# Grove_-_3-axis_analog_accelerometer.net
KiCad netlist of a schematic drawn in EAGLE
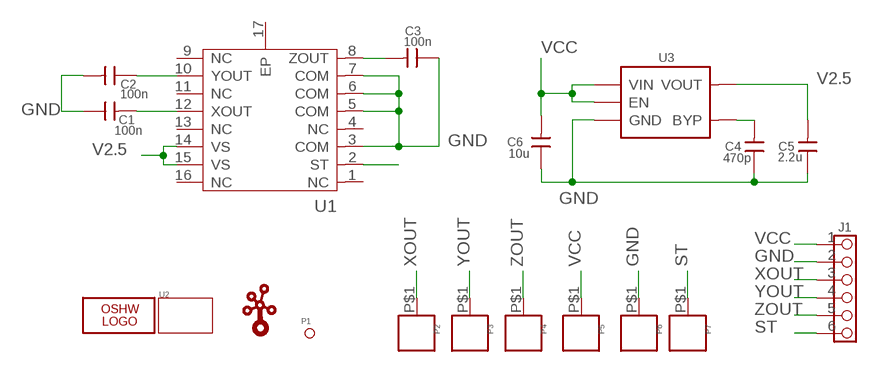
[diagram p0: schematic, sheet 1]

(export (version "E")
  (design (tool "Eeschema 10.0.6"))
  (components
    (comp (ref "C1")
      (value "100n")
      (footprint "eagle-import:0402")
      (libsource (lib "eagle-import") (part "C-0402"))
    )
    (comp (ref "C2")
      (value "100n")
      (footprint "eagle-import:0402")
      (libsource (lib "eagle-import") (part "C-0402"))
    )
    (comp (ref "C3")
      (value "100n")
      (footprint "eagle-import:0402")
      (libsource (lib "eagle-import") (part "C-0402"))
    )
    (comp (ref "C4")
      (value "470p")
      (footprint "eagle-import:0603")
      (libsource (lib "eagle-import") (part "C-0603"))
    )
    (comp (ref "C5")
      (value "2.2u")
      (footprint "eagle-import:0603")
      (libsource (lib "eagle-import") (part "C-0603"))
    )
    (comp (ref "C6")
      (value "10u")
      (footprint "eagle-import:0603")
      (libsource (lib "eagle-import") (part "C-0603"))
    )
    (comp (ref "J1")
      (value "HEADER-6P-60/35MIL")
      (footprint "eagle-import:6P-2.54-60_35MIL")
      (libsource (lib "eagle-import") (part "HEADER-6P-60/35MIL"))
    )
    (comp (ref "LOGO2")
      (value "LOGO-OSHW-6MILX0200-NT")
      (footprint "eagle-import:OSHW_6X200_NOTEXT")
      (libsource (lib "eagle-import") (part "LOGO-OSHW-6MILX0200-NT"))
    )
    (comp (ref "P1")
      (value "PAD-MARK")
      (footprint "eagle-import:ROUND-MARK-0.635")
      (libsource (lib "eagle-import") (part "PAD-MARK"))
    )
    (comp (ref "P2")
      (value "PAD'1X2MM'")
      (footprint "eagle-import:1P-1X2")
      (libsource (lib "eagle-import") (part "PAD'1X2MM'"))
    )
    (comp (ref "P3")
      (value "PAD'1X2MM'")
      (footprint "eagle-import:1P-1X2")
      (libsource (lib "eagle-import") (part "PAD'1X2MM'"))
    )
    (comp (ref "P4")
      (value "PAD'1X2MM'")
      (footprint "eagle-import:1P-1X2")
      (libsource (lib "eagle-import") (part "PAD'1X2MM'"))
    )
    (comp (ref "P5")
      (value "PAD'1X2MM'")
      (footprint "eagle-import:1P-1X2")
      (libsource (lib "eagle-import") (part "PAD'1X2MM'"))
    )
    (comp (ref "P6")
      (value "PAD'1X2MM'")
      (footprint "eagle-import:1P-1X2")
      (libsource (lib "eagle-import") (part "PAD'1X2MM'"))
    )
    (comp (ref "P7")
      (value "PAD'1X2MM'")
      (footprint "eagle-import:1P-1X2")
      (libsource (lib "eagle-import") (part "PAD'1X2MM'"))
    )
    (comp (ref "U$1")
      (value "LOGO-TWIGTWIGLOGO_SMALL")
      (footprint "eagle-import:TWIGLOGO_SMALL")
      (libsource (lib "eagle-import") (part "LOGO-TWIGTWIGLOGO_SMALL"))
    )
    (comp (ref "U1")
      (value "ADXL335")
      (footprint "eagle-import:LFCSP16-4X4")
      (libsource (lib "eagle-import") (part "ADXL335"))
    )
    (comp (ref "U2")
      (value "TWIG-1U")
      (footprint "eagle-import:1U-DIM-W_-DRILL")
      (libsource (lib "eagle-import") (part "TWIG-1U"))
    )
    (comp (ref "U3")
      (value "MIC5205")
      (footprint "eagle-import:SOT23-5")
      (libsource (lib "eagle-import") (part "MIC5205"))
    )
  )
  (nets
    (net (code "1") (name "/GND") (class "Default")
      (node (ref "C1") (pin "1") (pinfunction "1_1") (pintype "passive"))
      (node (ref "C2") (pin "2") (pinfunction "2_2") (pintype "passive"))
      (node (ref "C3") (pin "1") (pinfunction "1_1") (pintype "passive"))
      (node (ref "C4") (pin "1") (pinfunction "1_1") (pintype "passive"))
      (node (ref "C5") (pin "1") (pinfunction "1_1") (pintype "passive"))
      (node (ref "C6") (pin "1") (pinfunction "1_1") (pintype "passive"))
      (node (ref "J1") (pin "2") (pinfunction "2_2") (pintype "bidirectional"))
      (node (ref "P6") (pin "P$1") (pinfunction "P$1_P$1") (pintype "bidirectional"))
      (node (ref "U1") (pin "3") (pinfunction "COM_3") (pintype "bidirectional"))
      (node (ref "U1") (pin "5") (pinfunction "COM_5") (pintype "bidirectional"))
      (node (ref "U1") (pin "6") (pinfunction "COM_6") (pintype "bidirectional"))
      (node (ref "U1") (pin "7") (pinfunction "COM_7") (pintype "bidirectional"))
      (node (ref "U3") (pin "2") (pinfunction "GND_2") (pintype "bidirectional"))
    )
    (net (code "2") (name "/ST") (class "Default")
      (node (ref "J1") (pin "6") (pinfunction "6_6") (pintype "bidirectional"))
      (node (ref "P7") (pin "P$1") (pinfunction "P$1_P$1") (pintype "bidirectional"))
      (node (ref "U1") (pin "2") (pinfunction "ST_2") (pintype "bidirectional"))
    )
    (net (code "3") (name "/V2.5") (class "Default")
      (node (ref "C5") (pin "2") (pinfunction "2_2") (pintype "passive"))
      (node (ref "U1") (pin "14") (pinfunction "VS_14") (pintype "bidirectional"))
      (node (ref "U1") (pin "15") (pinfunction "VS_15") (pintype "bidirectional"))
      (node (ref "U3") (pin "5") (pinfunction "VOUT_5") (pintype "bidirectional"))
    )
    (net (code "4") (name "/VCC") (class "Default")
      (node (ref "C6") (pin "2") (pinfunction "2_2") (pintype "passive"))
      (node (ref "J1") (pin "1") (pinfunction "1_1") (pintype "bidirectional"))
      (node (ref "P5") (pin "P$1") (pinfunction "P$1_P$1") (pintype "bidirectional"))
      (node (ref "U3") (pin "1") (pinfunction "VIN_1") (pintype "bidirectional"))
      (node (ref "U3") (pin "3") (pinfunction "EN_3") (pintype "bidirectional"))
    )
    (net (code "5") (name "/XOUT") (class "Default")
      (node (ref "C1") (pin "2") (pinfunction "2_2") (pintype "passive"))
      (node (ref "J1") (pin "3") (pinfunction "3_3") (pintype "bidirectional"))
      (node (ref "P2") (pin "P$1") (pinfunction "P$1_P$1") (pintype "bidirectional"))
      (node (ref "U1") (pin "12") (pinfunction "XOUT_12") (pintype "bidirectional"))
    )
    (net (code "6") (name "/YOUT") (class "Default")
      (node (ref "C2") (pin "1") (pinfunction "1_1") (pintype "passive"))
      (node (ref "J1") (pin "4") (pinfunction "4_4") (pintype "bidirectional"))
      (node (ref "P3") (pin "P$1") (pinfunction "P$1_P$1") (pintype "bidirectional"))
      (node (ref "U1") (pin "10") (pinfunction "YOUT_10") (pintype "bidirectional"))
    )
    (net (code "7") (name "/ZOUT") (class "Default")
      (node (ref "C3") (pin "2") (pinfunction "2_2") (pintype "passive"))
      (node (ref "J1") (pin "5") (pinfunction "5_5") (pintype "bidirectional"))
      (node (ref "P4") (pin "P$1") (pinfunction "P$1_P$1") (pintype "bidirectional"))
      (node (ref "U1") (pin "8") (pinfunction "ZOUT_8") (pintype "bidirectional"))
    )
    (net (code "8") (name "Net-(U3-BYP)") (class "Default")
      (node (ref "C4") (pin "2") (pinfunction "2_2") (pintype "passive"))
      (node (ref "U3") (pin "4") (pinfunction "BYP_4") (pintype "bidirectional"))
    )
    (net (code "9") (name "unconnected-(U1-EP-Pad17)") (class "Default")
      (node (ref "U1") (pin "17") (pinfunction "EP_17") (pintype "bidirectional"))
    )
    (net (code "10") (name "unconnected-(U1-NC-Pad1)") (class "Default")
      (node (ref "U1") (pin "1") (pinfunction "NC_1") (pintype "no_connect"))
    )
    (net (code "11") (name "unconnected-(U1-NC-Pad4)") (class "Default")
      (node (ref "U1") (pin "4") (pinfunction "NC_4") (pintype "no_connect"))
    )
    (net (code "12") (name "unconnected-(U1-NC-Pad9)") (class "Default")
      (node (ref "U1") (pin "9") (pinfunction "NC_9") (pintype "no_connect"))
    )
    (net (code "13") (name "unconnected-(U1-NC-Pad11)") (class "Default")
      (node (ref "U1") (pin "11") (pinfunction "NC_11") (pintype "no_connect"))
    )
    (net (code "14") (name "unconnected-(U1-NC-Pad13)") (class "Default")
      (node (ref "U1") (pin "13") (pinfunction "NC_13") (pintype "no_connect"))
    )
    (net (code "15") (name "unconnected-(U1-NC-Pad16)") (class "Default")
      (node (ref "U1") (pin "16") (pinfunction "NC_16") (pintype "no_connect"))
    )
  )
)
